# mcu_brd2.net
KiCad netlist of a schematic drawn in EAGLE
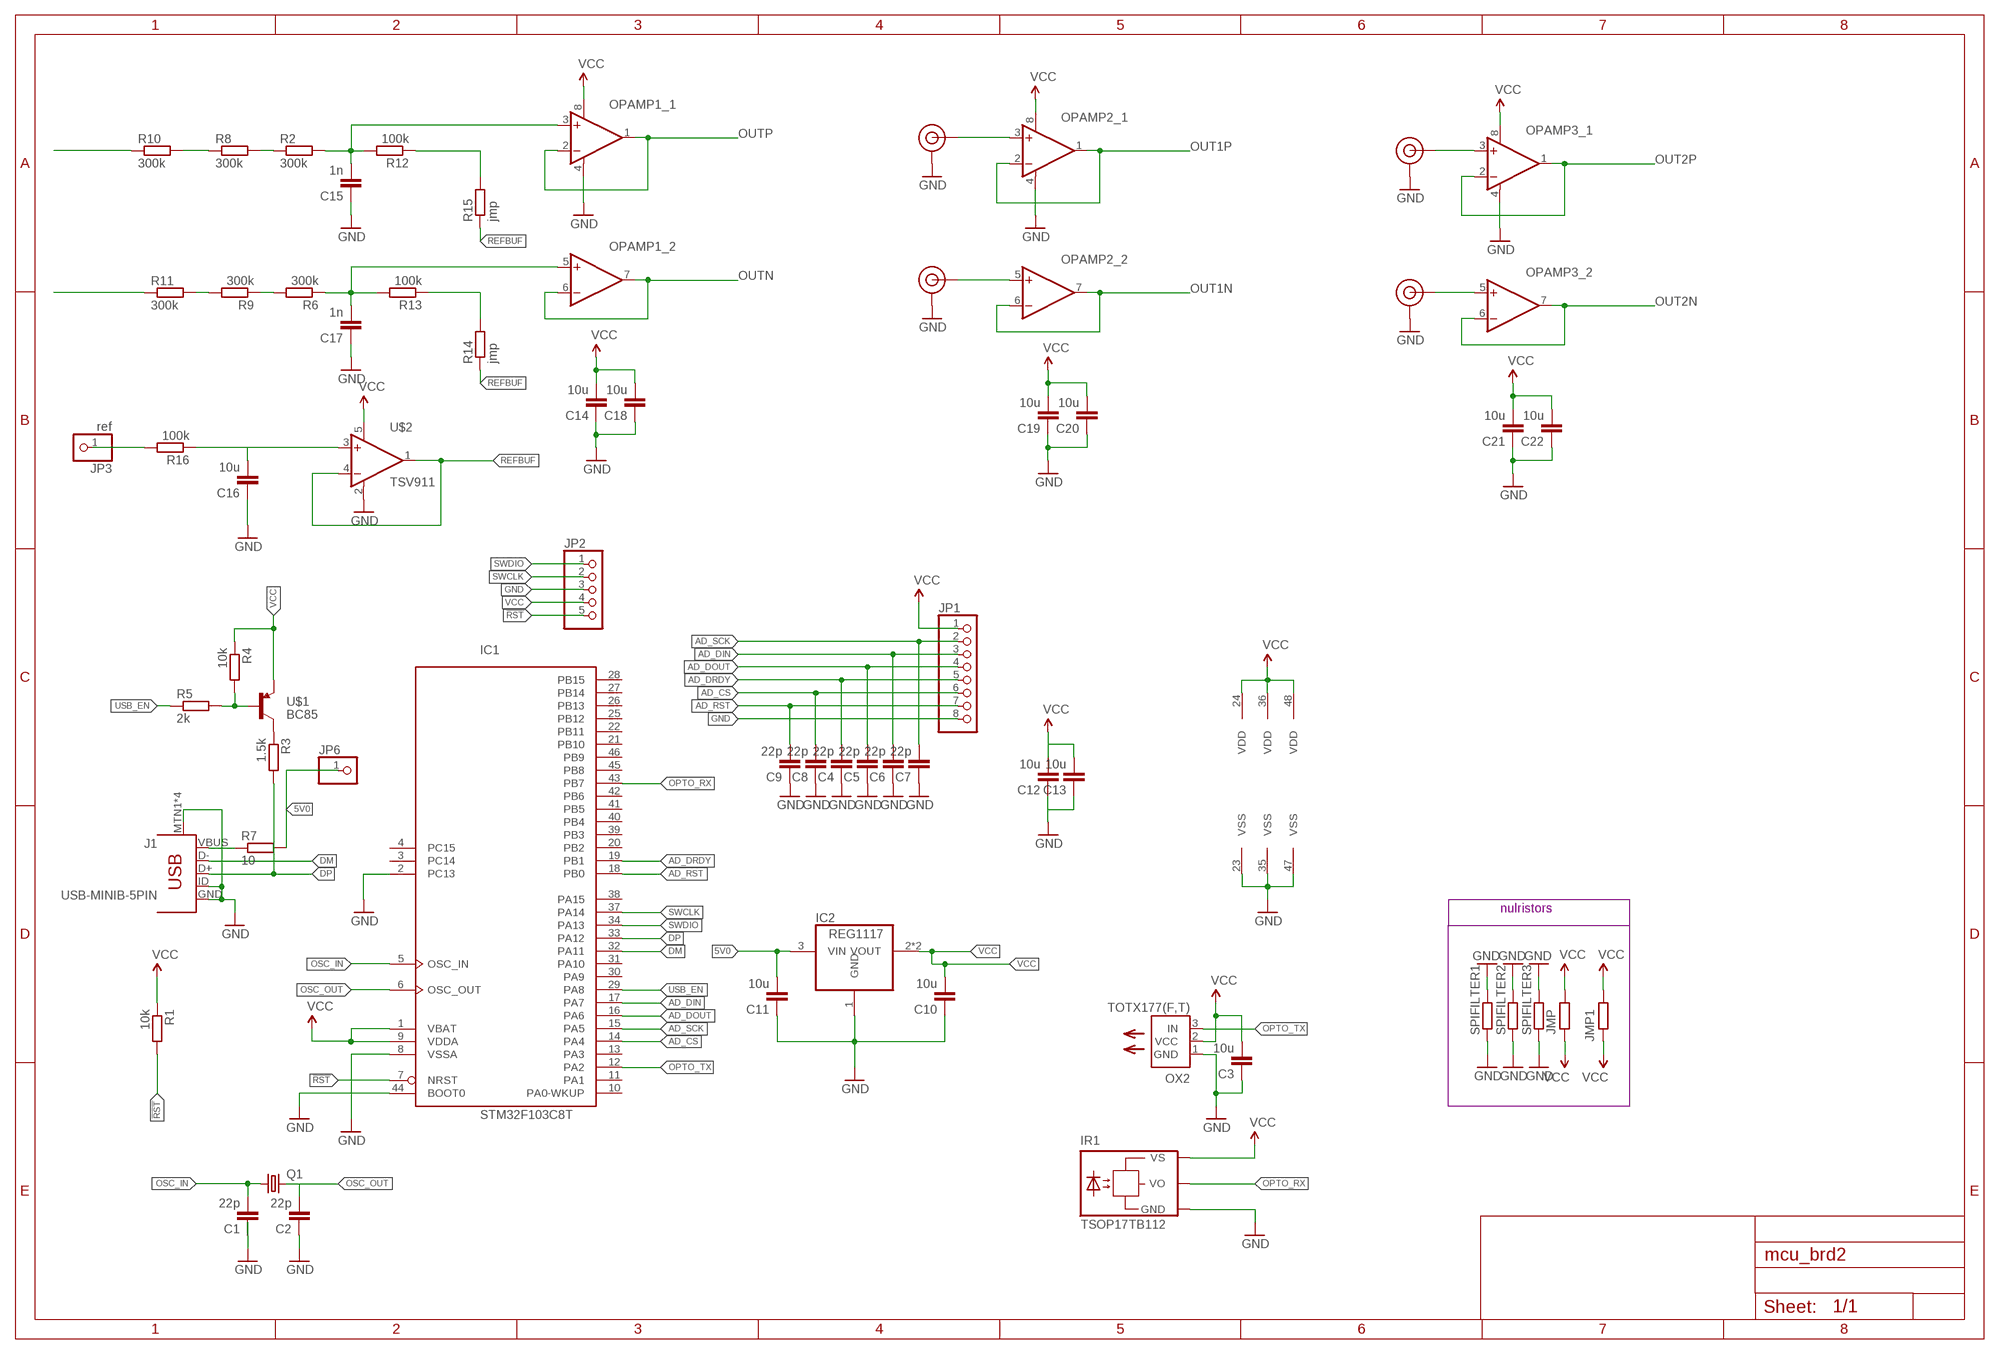
[diagram p0: schematic, sheet 1]

(export (version "E")
  (design (tool "Eeschema 10.0.6"))
  (components
    (comp (ref "C1")
      (value "22p")
      (footprint "eagle-import:C0603")
      (libsource (lib "eagle-import") (part "CC0603"))
    )
    (comp (ref "C2")
      (value "22p")
      (footprint "eagle-import:C0603")
      (libsource (lib "eagle-import") (part "CC0603"))
    )
    (comp (ref "C3")
      (value "10u")
      (footprint "eagle-import:C0603")
      (libsource (lib "eagle-import") (part "CC0603"))
    )
    (comp (ref "C4")
      (value "22p")
      (footprint "eagle-import:C0603")
      (libsource (lib "eagle-import") (part "CC0603"))
    )
    (comp (ref "C5")
      (value "22p")
      (footprint "eagle-import:C0603")
      (libsource (lib "eagle-import") (part "CC0603"))
    )
    (comp (ref "C6")
      (value "22p")
      (footprint "eagle-import:C0603")
      (libsource (lib "eagle-import") (part "CC0603"))
    )
    (comp (ref "C7")
      (value "22p")
      (footprint "eagle-import:C0603")
      (libsource (lib "eagle-import") (part "CC0603"))
    )
    (comp (ref "C8")
      (value "22p")
      (footprint "eagle-import:C0603")
      (libsource (lib "eagle-import") (part "CC0603"))
    )
    (comp (ref "C9")
      (value "22p")
      (footprint "eagle-import:C0603")
      (libsource (lib "eagle-import") (part "CC0603"))
    )
    (comp (ref "C10")
      (value "10u")
      (footprint "eagle-import:C0805")
      (libsource (lib "eagle-import") (part "CC0805"))
    )
    (comp (ref "C11")
      (value "10u")
      (footprint "eagle-import:C0805")
      (libsource (lib "eagle-import") (part "CC0805"))
    )
    (comp (ref "C12")
      (value "10u")
      (footprint "eagle-import:C0805")
      (libsource (lib "eagle-import") (part "CC0805"))
    )
    (comp (ref "C13")
      (value "10u")
      (footprint "eagle-import:C0805")
      (libsource (lib "eagle-import") (part "CC0805"))
    )
    (comp (ref "C14")
      (value "10u")
      (footprint "eagle-import:C0805")
      (libsource (lib "eagle-import") (part "CC0805"))
    )
    (comp (ref "C15")
      (value "1n")
      (footprint "eagle-import:C0603")
      (libsource (lib "eagle-import") (part "CC0603"))
    )
    (comp (ref "C16")
      (value "10u")
      (footprint "eagle-import:C0805")
      (libsource (lib "eagle-import") (part "CC0805"))
    )
    (comp (ref "C17")
      (value "1n")
      (footprint "eagle-import:C0603")
      (libsource (lib "eagle-import") (part "CC0603"))
    )
    (comp (ref "C18")
      (value "10u")
      (footprint "eagle-import:C0805")
      (libsource (lib "eagle-import") (part "CC0805"))
    )
    (comp (ref "C19")
      (value "10u")
      (footprint "eagle-import:C0805")
      (libsource (lib "eagle-import") (part "CC0805"))
    )
    (comp (ref "C20")
      (value "10u")
      (footprint "eagle-import:C0805")
      (libsource (lib "eagle-import") (part "CC0805"))
    )
    (comp (ref "C21")
      (value "10u")
      (footprint "eagle-import:C0805")
      (libsource (lib "eagle-import") (part "CC0805"))
    )
    (comp (ref "C22")
      (value "10u")
      (footprint "eagle-import:C0805")
      (libsource (lib "eagle-import") (part "CC0805"))
    )
    (comp (ref "IC1")
      (value "STM32F103C8T")
      (footprint "eagle-import:LQFP48")
      (libsource (lib "eagle-import") (part "STM32F103CT8"))
    )
    (comp (ref "IC2")
      (value "REG1117")
      (footprint "eagle-import:SOT223")
      (libsource (lib "eagle-import") (part "REG1117"))
    )
    (comp (ref "IR1")
      (value "TSOP17TB112")
      (footprint "eagle-import:1X03")
      (libsource (lib "eagle-import") (part "TSOP17TB112"))
    )
    (comp (ref "J$1")
      (value "SMA_EDGE")
      (footprint "eagle-import:SMA-EDGE")
      (libsource (lib "eagle-import") (part "SMA_EDGE"))
    )
    (comp (ref "J$2")
      (value "SMA_EDGE")
      (footprint "eagle-import:SMA-EDGE")
      (libsource (lib "eagle-import") (part "SMA_EDGE"))
    )
    (comp (ref "J$3")
      (value "SMA_EDGE")
      (footprint "eagle-import:SMA-EDGE")
      (libsource (lib "eagle-import") (part "SMA_EDGE"))
    )
    (comp (ref "J$4")
      (value "SMA_EDGE")
      (footprint "eagle-import:SMA-EDGE")
      (libsource (lib "eagle-import") (part "SMA_EDGE"))
    )
    (comp (ref "J1")
      (value "USB-MINIB-5PIN")
      (footprint "eagle-import:USB-MINIB")
      (libsource (lib "eagle-import") (part "USB-MINIB-5PIN"))
    )
    (comp (ref "JMP")
      (value "R0603")
      (footprint "eagle-import:0603")
      (libsource (lib "eagle-import") (part "R0603"))
    )
    (comp (ref "JMP1")
      (value "R0603")
      (footprint "eagle-import:0603")
      (libsource (lib "eagle-import") (part "R0603"))
    )
    (comp (ref "JP1")
      (value "PINHD-1X8")
      (footprint "eagle-import:1X08")
      (libsource (lib "eagle-import") (part "PINHD-1X8"))
    )
    (comp (ref "JP2")
      (value "PINHD-1X5")
      (footprint "eagle-import:1X05")
      (libsource (lib "eagle-import") (part "PINHD-1X5"))
    )
    (comp (ref "JP3")
      (value "ref")
      (footprint "eagle-import:1X01M")
      (libsource (lib "eagle-import") (part "PINHD-1X01_2.00"))
    )
    (comp (ref "JP6")
      (value "PINHD-1X1")
      (footprint "eagle-import:1X01")
      (libsource (lib "eagle-import") (part "PINHD-1X1"))
    )
    (comp (ref "OPAMP1")
      (value "LMC662")
      (footprint "eagle-import:SO08")
      (libsource (lib "eagle-import") (part "LMC662"))
    )
    (comp (ref "OPAMP2")
      (value "LMC662")
      (footprint "eagle-import:SO08")
      (libsource (lib "eagle-import") (part "LMC662"))
    )
    (comp (ref "OPAMP3")
      (value "LMC662")
      (footprint "eagle-import:SO08")
      (libsource (lib "eagle-import") (part "LMC662"))
    )
    (comp (ref "OX2")
      (value "TOTX177(F,T)")
      (footprint "eagle-import:TOTX")
      (libsource (lib "eagle-import") (part "TOTX177(F,T)"))
    )
    (comp (ref "Q1")
      (value "CRYSTALHC49UP")
      (footprint "eagle-import:HC49UP")
      (libsource (lib "eagle-import") (part "CRYSTALHC49UP"))
    )
    (comp (ref "R1")
      (value "10k")
      (footprint "eagle-import:0603")
      (libsource (lib "eagle-import") (part "R0603"))
    )
    (comp (ref "R2")
      (value "300k")
      (footprint "eagle-import:0603")
      (libsource (lib "eagle-import") (part "R0603"))
    )
    (comp (ref "R3")
      (value "1.5k")
      (footprint "eagle-import:0603")
      (libsource (lib "eagle-import") (part "R0603"))
    )
    (comp (ref "R4")
      (value "10k")
      (footprint "eagle-import:0603")
      (libsource (lib "eagle-import") (part "R0603"))
    )
    (comp (ref "R5")
      (value "2k")
      (footprint "eagle-import:0603")
      (libsource (lib "eagle-import") (part "R0603"))
    )
    (comp (ref "R6")
      (value "300k")
      (footprint "eagle-import:0603")
      (libsource (lib "eagle-import") (part "R0603"))
    )
    (comp (ref "R7")
      (value "10")
      (footprint "eagle-import:R0805")
      (libsource (lib "eagle-import") (part "R0805"))
    )
    (comp (ref "R8")
      (value "300k")
      (footprint "eagle-import:0603")
      (libsource (lib "eagle-import") (part "R0603"))
    )
    (comp (ref "R9")
      (value "300k")
      (footprint "eagle-import:0603")
      (libsource (lib "eagle-import") (part "R0603"))
    )
    (comp (ref "R10")
      (value "300k")
      (footprint "eagle-import:0603")
      (libsource (lib "eagle-import") (part "R0603"))
    )
    (comp (ref "R11")
      (value "300k")
      (footprint "eagle-import:0603")
      (libsource (lib "eagle-import") (part "R0603"))
    )
    (comp (ref "R12")
      (value "100k")
      (footprint "eagle-import:0603")
      (libsource (lib "eagle-import") (part "R0603"))
    )
    (comp (ref "R13")
      (value "100k")
      (footprint "eagle-import:0603")
      (libsource (lib "eagle-import") (part "R0603"))
    )
    (comp (ref "R14")
      (value "jmp")
      (footprint "eagle-import:0603")
      (libsource (lib "eagle-import") (part "R0603"))
    )
    (comp (ref "R15")
      (value "jmp")
      (footprint "eagle-import:0603")
      (libsource (lib "eagle-import") (part "R0603"))
    )
    (comp (ref "R16")
      (value "100k")
      (footprint "eagle-import:0603")
      (libsource (lib "eagle-import") (part "R0603"))
    )
    (comp (ref "SPIFILTER1")
      (value "R0603")
      (footprint "eagle-import:0603")
      (libsource (lib "eagle-import") (part "R0603"))
    )
    (comp (ref "SPIFILTER2")
      (value "R0603")
      (footprint "eagle-import:0603")
      (libsource (lib "eagle-import") (part "R0603"))
    )
    (comp (ref "SPIFILTER3")
      (value "R0603")
      (footprint "eagle-import:0603")
      (libsource (lib "eagle-import") (part "R0603"))
    )
    (comp (ref "U$1")
      (value "BC85")
      (footprint "eagle-import:SOT23")
      (libsource (lib "eagle-import") (part "BC85"))
    )
    (comp (ref "U$2")
      (value "TSV911")
      (footprint "eagle-import:SOT23-5L")
      (libsource (lib "eagle-import") (part "TSV911"))
    )
  )
  (nets
    (net (code "1") (name "/OUT1N") (class "Default")
      (node (ref "OPAMP2") (pin "6") (pinfunction "-IN_6") (pintype "input"))
      (node (ref "OPAMP2") (pin "7") (pinfunction "OUT_7") (pintype "output"))
    )
    (net (code "2") (name "/OUT1P") (class "Default")
      (node (ref "OPAMP2") (pin "1") (pinfunction "OUT_1") (pintype "output"))
      (node (ref "OPAMP2") (pin "2") (pinfunction "-IN_2") (pintype "input"))
    )
    (net (code "3") (name "/OUT2N") (class "Default")
      (node (ref "OPAMP3") (pin "6") (pinfunction "-IN_6") (pintype "input"))
      (node (ref "OPAMP3") (pin "7") (pinfunction "OUT_7") (pintype "output"))
    )
    (net (code "4") (name "/OUT2P") (class "Default")
      (node (ref "OPAMP3") (pin "1") (pinfunction "OUT_1") (pintype "output"))
      (node (ref "OPAMP3") (pin "2") (pinfunction "-IN_2") (pintype "input"))
    )
    (net (code "5") (name "/OUTN") (class "Default")
      (node (ref "OPAMP1") (pin "6") (pinfunction "-IN_6") (pintype "input"))
      (node (ref "OPAMP1") (pin "7") (pinfunction "OUT_7") (pintype "output"))
    )
    (net (code "6") (name "/OUTP") (class "Default")
      (node (ref "OPAMP1") (pin "1") (pinfunction "OUT_1") (pintype "output"))
      (node (ref "OPAMP1") (pin "2") (pinfunction "-IN_2") (pintype "input"))
    )
    (net (code "7") (name "/~{RST}") (class "Default")
      (node (ref "IC1") (pin "7") (pinfunction "NRST_7") (pintype "bidirectional"))
      (node (ref "JP2") (pin "5") (pinfunction "5_5") (pintype "passive"))
      (node (ref "R1") (pin "2") (pinfunction "2_2") (pintype "passive"))
    )
    (net (code "8") (name "5V0") (class "Default")
      (node (ref "C11") (pin "2") (pinfunction "2_2") (pintype "passive"))
      (node (ref "IC2") (pin "3") (pinfunction "VIN_3") (pintype "input"))
      (node (ref "JP6") (pin "1") (pinfunction "1_1") (pintype "passive"))
      (node (ref "R7") (pin "2") (pinfunction "2_2") (pintype "passive"))
    )
    (net (code "9") (name "AD_CS") (class "Default")
      (node (ref "C8") (pin "2") (pinfunction "2_2") (pintype "passive"))
      (node (ref "IC1") (pin "14") (pinfunction "PA4_14") (pintype "bidirectional"))
      (node (ref "JP1") (pin "6") (pinfunction "6_6") (pintype "passive"))
    )
    (net (code "10") (name "AD_DIN") (class "Default")
      (node (ref "C6") (pin "2") (pinfunction "2_2") (pintype "passive"))
      (node (ref "IC1") (pin "17") (pinfunction "PA7_17") (pintype "bidirectional"))
      (node (ref "JP1") (pin "3") (pinfunction "3_3") (pintype "passive"))
    )
    (net (code "11") (name "AD_DOUT") (class "Default")
      (node (ref "C5") (pin "2") (pinfunction "2_2") (pintype "passive"))
      (node (ref "IC1") (pin "16") (pinfunction "PA6_16") (pintype "bidirectional"))
      (node (ref "JP1") (pin "4") (pinfunction "4_4") (pintype "passive"))
    )
    (net (code "12") (name "AD_DRDY") (class "Default")
      (node (ref "C4") (pin "2") (pinfunction "2_2") (pintype "passive"))
      (node (ref "IC1") (pin "19") (pinfunction "PB1_19") (pintype "bidirectional"))
      (node (ref "JP1") (pin "5") (pinfunction "5_5") (pintype "passive"))
    )
    (net (code "13") (name "AD_RST") (class "Default")
      (node (ref "C9") (pin "2") (pinfunction "2_2") (pintype "passive"))
      (node (ref "IC1") (pin "18") (pinfunction "PB0_18") (pintype "bidirectional"))
      (node (ref "JP1") (pin "7") (pinfunction "7_7") (pintype "passive"))
    )
    (net (code "14") (name "AD_SCK") (class "Default")
      (node (ref "C7") (pin "2") (pinfunction "2_2") (pintype "passive"))
      (node (ref "IC1") (pin "15") (pinfunction "PA5_15") (pintype "bidirectional"))
      (node (ref "JP1") (pin "2") (pinfunction "2_2") (pintype "passive"))
    )
    (net (code "15") (name "DM") (class "Default")
      (node (ref "IC1") (pin "32") (pinfunction "PA11_32") (pintype "bidirectional"))
      (node (ref "J1") (pin "D-") (pinfunction "D-_D-") (pintype "bidirectional"))
    )
    (net (code "16") (name "DP") (class "Default")
      (node (ref "IC1") (pin "33") (pinfunction "PA12_33") (pintype "bidirectional"))
      (node (ref "J1") (pin "D+") (pinfunction "D+_D+") (pintype "bidirectional"))
      (node (ref "R3") (pin "2") (pinfunction "2_2") (pintype "passive"))
    )
    (net (code "17") (name "GND") (class "Default")
      (node (ref "C1") (pin "1") (pinfunction "1_1") (pintype "passive"))
      (node (ref "C10") (pin "1") (pinfunction "1_1") (pintype "passive"))
      (node (ref "C11") (pin "1") (pinfunction "1_1") (pintype "passive"))
      (node (ref "C12") (pin "1") (pinfunction "1_1") (pintype "passive"))
      (node (ref "C13") (pin "1") (pinfunction "1_1") (pintype "passive"))
      (node (ref "C14") (pin "1") (pinfunction "1_1") (pintype "passive"))
      (node (ref "C15") (pin "1") (pinfunction "1_1") (pintype "passive"))
      (node (ref "C16") (pin "1") (pinfunction "1_1") (pintype "passive"))
      (node (ref "C17") (pin "1") (pinfunction "1_1") (pintype "passive"))
      (node (ref "C18") (pin "1") (pinfunction "1_1") (pintype "passive"))
      (node (ref "C19") (pin "1") (pinfunction "1_1") (pintype "passive"))
      (node (ref "C2") (pin "1") (pinfunction "1_1") (pintype "passive"))
      (node (ref "C20") (pin "1") (pinfunction "1_1") (pintype "passive"))
      (node (ref "C21") (pin "1") (pinfunction "1_1") (pintype "passive"))
      (node (ref "C22") (pin "1") (pinfunction "1_1") (pintype "passive"))
      (node (ref "C3") (pin "1") (pinfunction "1_1") (pintype "passive"))
      (node (ref "C4") (pin "1") (pinfunction "1_1") (pintype "passive"))
      (node (ref "C5") (pin "1") (pinfunction "1_1") (pintype "passive"))
      (node (ref "C6") (pin "1") (pinfunction "1_1") (pintype "passive"))
      (node (ref "C7") (pin "1") (pinfunction "1_1") (pintype "passive"))
      (node (ref "C8") (pin "1") (pinfunction "1_1") (pintype "passive"))
      (node (ref "C9") (pin "1") (pinfunction "1_1") (pintype "passive"))
      (node (ref "IC1") (pin "2") (pinfunction "PC13_2") (pintype "bidirectional"))
      (node (ref "IC1") (pin "23") (pinfunction "VSS_23") (pintype "power_in"))
      (node (ref "IC1") (pin "35") (pinfunction "VSS_35") (pintype "power_in"))
      (node (ref "IC1") (pin "44") (pinfunction "BOOT0_44") (pintype "input"))
      (node (ref "IC1") (pin "47") (pinfunction "VSS_47") (pintype "power_in"))
      (node (ref "IC1") (pin "8") (pinfunction "VSSA_8") (pintype "power_in"))
      (node (ref "IC2") (pin "1") (pinfunction "GND_1") (pintype "power_in"))
      (node (ref "IR1") (pin "3") (pinfunction "GND_3") (pintype "power_in"))
      (node (ref "J$1") (pin "GND@0") (pinfunction "GND_GND@0") (pintype "bidirectional"))
      (node (ref "J$1") (pin "GND@1") (pinfunction "GND_GND@1") (pintype "bidirectional"))
      (node (ref "J$1") (pin "GND@2") (pinfunction "GND_GND@2") (pintype "bidirectional"))
      (node (ref "J$1") (pin "GND@3") (pinfunction "GND_GND@3") (pintype "bidirectional"))
      (node (ref "J$2") (pin "GND@0") (pinfunction "GND_GND@0") (pintype "bidirectional"))
      (node (ref "J$2") (pin "GND@1") (pinfunction "GND_GND@1") (pintype "bidirectional"))
      (node (ref "J$2") (pin "GND@2") (pinfunction "GND_GND@2") (pintype "bidirectional"))
      (node (ref "J$2") (pin "GND@3") (pinfunction "GND_GND@3") (pintype "bidirectional"))
      (node (ref "J$3") (pin "GND@0") (pinfunction "GND_GND@0") (pintype "bidirectional"))
      (node (ref "J$3") (pin "GND@1") (pinfunction "GND_GND@1") (pintype "bidirectional"))
      (node (ref "J$3") (pin "GND@2") (pinfunction "GND_GND@2") (pintype "bidirectional"))
      (node (ref "J$3") (pin "GND@3") (pinfunction "GND_GND@3") (pintype "bidirectional"))
      (node (ref "J$4") (pin "GND@0") (pinfunction "GND_GND@0") (pintype "bidirectional"))
      (node (ref "J$4") (pin "GND@1") (pinfunction "GND_GND@1") (pintype "bidirectional"))
      (node (ref "J$4") (pin "GND@2") (pinfunction "GND_GND@2") (pintype "bidirectional"))
      (node (ref "J$4") (pin "GND@3") (pinfunction "GND_GND@3") (pintype "bidirectional"))
      (node (ref "J1") (pin "GND") (pinfunction "GND_GND") (pintype "bidirectional"))
      (node (ref "J1") (pin "ID") (pinfunction "ID_ID") (pintype "bidirectional"))
      (node (ref "J1") (pin "MTN1") (pinfunction "MTN1_MTN1") (pintype "bidirectional"))
      (node (ref "J1") (pin "MTN2") (pinfunction "MTN1_MTN2") (pintype "bidirectional"))
      (node (ref "J1") (pin "MTN3") (pinfunction "MTN1_MTN3") (pintype "bidirectional"))
      (node (ref "J1") (pin "MTN4") (pinfunction "MTN1_MTN4") (pintype "bidirectional"))
      (node (ref "JP1") (pin "8") (pinfunction "8_8") (pintype "passive"))
      (node (ref "JP2") (pin "3") (pinfunction "3_3") (pintype "passive"))
      (node (ref "OPAMP1") (pin "4") (pinfunction "V-_4") (pintype "power_in"))
      (node (ref "OPAMP2") (pin "4") (pinfunction "V-_4") (pintype "power_in"))
      (node (ref "OPAMP3") (pin "4") (pinfunction "V-_4") (pintype "power_in"))
      (node (ref "OX2") (pin "1") (pinfunction "GND_1") (pintype "power_in"))
      (node (ref "SPIFILTER1") (pin "1") (pinfunction "1_1") (pintype "passive"))
      (node (ref "SPIFILTER1") (pin "2") (pinfunction "2_2") (pintype "passive"))
      (node (ref "SPIFILTER2") (pin "1") (pinfunction "1_1") (pintype "passive"))
      (node (ref "SPIFILTER2") (pin "2") (pinfunction "2_2") (pintype "passive"))
      (node (ref "SPIFILTER3") (pin "1") (pinfunction "1_1") (pintype "passive"))
      (node (ref "SPIFILTER3") (pin "2") (pinfunction "2_2") (pintype "passive"))
      (node (ref "U$2") (pin "2") (pinfunction "V-_2") (pintype "power_in"))
    )
    (net (code "18") (name "Net-(J$1-SIGNAL)") (class "Default")
      (node (ref "J$1") (pin "SIG") (pinfunction "SIGNAL_SIG") (pintype "bidirectional"))
      (node (ref "OPAMP2") (pin "3") (pinfunction "+IN_3") (pintype "input"))
    )
    (net (code "19") (name "Net-(J$2-SIGNAL)") (class "Default")
      (node (ref "J$2") (pin "SIG") (pinfunction "SIGNAL_SIG") (pintype "bidirectional"))
      (node (ref "OPAMP2") (pin "5") (pinfunction "+IN_5") (pintype "input"))
    )
    (net (code "20") (name "Net-(J$3-SIGNAL)") (class "Default")
      (node (ref "J$3") (pin "SIG") (pinfunction "SIGNAL_SIG") (pintype "bidirectional"))
      (node (ref "OPAMP3") (pin "3") (pinfunction "+IN_3") (pintype "input"))
    )
    (net (code "21") (name "Net-(J$4-SIGNAL)") (class "Default")
      (node (ref "J$4") (pin "SIG") (pinfunction "SIGNAL_SIG") (pintype "bidirectional"))
      (node (ref "OPAMP3") (pin "5") (pinfunction "+IN_5") (pintype "input"))
    )
    (net (code "22") (name "Net-(J1-PadVBUS)") (class "Default")
      (node (ref "J1") (pin "VBUS") (pinfunction "VBUS_VBUS") (pintype "bidirectional"))
      (node (ref "R7") (pin "1") (pinfunction "1_1") (pintype "passive"))
    )
    (net (code "23") (name "Net-(JP3-Pad1)") (class "Default")
      (node (ref "JP3") (pin "1") (pinfunction "1_1") (pintype "passive"))
      (node (ref "R16") (pin "2") (pinfunction "2_2") (pintype "passive"))
    )
    (net (code "24") (name "Net-(OPAMP1A-+IN)") (class "Default")
      (node (ref "C15") (pin "2") (pinfunction "2_2") (pintype "passive"))
      (node (ref "OPAMP1") (pin "3") (pinfunction "+IN_3") (pintype "input"))
      (node (ref "R12") (pin "2") (pinfunction "2_2") (pintype "passive"))
      (node (ref "R2") (pin "2") (pinfunction "2_2") (pintype "passive"))
    )
    (net (code "25") (name "Net-(OPAMP1B-+IN)") (class "Default")
      (node (ref "C17") (pin "2") (pinfunction "2_2") (pintype "passive"))
      (node (ref "OPAMP1") (pin "5") (pinfunction "+IN_5") (pintype "input"))
      (node (ref "R13") (pin "2") (pinfunction "2_2") (pintype "passive"))
      (node (ref "R6") (pin "1") (pinfunction "1_1") (pintype "passive"))
    )
    (net (code "26") (name "Net-(R2-Pad1)") (class "Default")
      (node (ref "R2") (pin "1") (pinfunction "1_1") (pintype "passive"))
      (node (ref "R8") (pin "2") (pinfunction "2_2") (pintype "passive"))
    )
    (net (code "27") (name "Net-(R6-Pad2)") (class "Default")
      (node (ref "R6") (pin "2") (pinfunction "2_2") (pintype "passive"))
      (node (ref "R9") (pin "1") (pinfunction "1_1") (pintype "passive"))
    )
    (net (code "28") (name "Net-(R10-Pad2)") (class "Default")
      (node (ref "R10") (pin "2") (pinfunction "2_2") (pintype "passive"))
      (node (ref "R8") (pin "1") (pinfunction "1_1") (pintype "passive"))
    )
    (net (code "29") (name "Net-(R11-Pad2)") (class "Default")
      (node (ref "R11") (pin "2") (pinfunction "2_2") (pintype "passive"))
      (node (ref "R9") (pin "2") (pinfunction "2_2") (pintype "passive"))
    )
    (net (code "30") (name "Net-(R12-Pad1)") (class "Default")
      (node (ref "R12") (pin "1") (pinfunction "1_1") (pintype "passive"))
      (node (ref "R15") (pin "2") (pinfunction "2_2") (pintype "passive"))
    )
    (net (code "31") (name "Net-(R13-Pad1)") (class "Default")
      (node (ref "R13") (pin "1") (pinfunction "1_1") (pintype "passive"))
      (node (ref "R14") (pin "2") (pinfunction "2_2") (pintype "passive"))
    )
    (net (code "32") (name "Net-(U$1-B)") (class "Default")
      (node (ref "R4") (pin "2") (pinfunction "2_2") (pintype "passive"))
      (node (ref "R5") (pin "2") (pinfunction "2_2") (pintype "passive"))
      (node (ref "U$1") (pin "1") (pinfunction "B_1") (pintype "passive"))
    )
    (net (code "33") (name "Net-(U$1-C)") (class "Default")
      (node (ref "R3") (pin "1") (pinfunction "1_1") (pintype "passive"))
      (node (ref "U$1") (pin "3") (pinfunction "C_3") (pintype "passive"))
    )
    (net (code "34") (name "Net-(U$2-+IN)") (class "Default")
      (node (ref "C16") (pin "2") (pinfunction "2_2") (pintype "passive"))
      (node (ref "R16") (pin "1") (pinfunction "1_1") (pintype "passive"))
      (node (ref "U$2") (pin "3") (pinfunction "+IN_3") (pintype "input"))
    )
    (net (code "35") (name "OPTO_RX") (class "Default")
      (node (ref "IC1") (pin "43") (pinfunction "PB7_43") (pintype "bidirectional"))
      (node (ref "IR1") (pin "1") (pinfunction "VO_1") (pintype "open_collector"))
    )
    (net (code "36") (name "OPTO_TX") (class "Default")
      (node (ref "IC1") (pin "12") (pinfunction "PA2_12") (pintype "bidirectional"))
      (node (ref "OX2") (pin "3") (pinfunction "IN_3") (pintype "input"))
    )
    (net (code "37") (name "OSC_IN") (class "Default")
      (node (ref "C1") (pin "2") (pinfunction "2_2") (pintype "passive"))
      (node (ref "IC1") (pin "5") (pinfunction "OSC_IN_5") (pintype "bidirectional"))
      (node (ref "Q1") (pin "1") (pinfunction "1_1") (pintype "passive"))
    )
    (net (code "38") (name "OSC_OUT") (class "Default")
      (node (ref "C2") (pin "2") (pinfunction "2_2") (pintype "passive"))
      (node (ref "IC1") (pin "6") (pinfunction "OSC_OUT_6") (pintype "bidirectional"))
      (node (ref "Q1") (pin "2") (pinfunction "2_2") (pintype "passive"))
    )
    (net (code "39") (name "REFBUF") (class "Default")
      (node (ref "R14") (pin "1") (pinfunction "1_1") (pintype "passive"))
      (node (ref "R15") (pin "1") (pinfunction "1_1") (pintype "passive"))
      (node (ref "U$2") (pin "1") (pinfunction "OUT_1") (pintype "output"))
      (node (ref "U$2") (pin "4") (pinfunction "-IN_4") (pintype "input"))
    )
    (net (code "40") (name "SWCLK") (class "Default")
      (node (ref "IC1") (pin "37") (pinfunction "PA14_37") (pintype "bidirectional"))
      (node (ref "JP2") (pin "2") (pinfunction "2_2") (pintype "passive"))
    )
    (net (code "41") (name "SWDIO") (class "Default")
      (node (ref "IC1") (pin "34") (pinfunction "PA13_34") (pintype "bidirectional"))
      (node (ref "JP2") (pin "1") (pinfunction "1_1") (pintype "passive"))
    )
    (net (code "42") (name "USB_EN") (class "Default")
      (node (ref "IC1") (pin "29") (pinfunction "PA8_29") (pintype "bidirectional"))
      (node (ref "R5") (pin "1") (pinfunction "1_1") (pintype "passive"))
    )
    (net (code "43") (name "VCC") (class "Default")
      (node (ref "C10") (pin "2") (pinfunction "2_2") (pintype "passive"))
      (node (ref "C12") (pin "2") (pinfunction "2_2") (pintype "passive"))
      (node (ref "C13") (pin "2") (pinfunction "2_2") (pintype "passive"))
      (node (ref "C14") (pin "2") (pinfunction "2_2") (pintype "passive"))
      (node (ref "C18") (pin "2") (pinfunction "2_2") (pintype "passive"))
      (node (ref "C19") (pin "2") (pinfunction "2_2") (pintype "passive"))
      (node (ref "C20") (pin "2") (pinfunction "2_2") (pintype "passive"))
      (node (ref "C21") (pin "2") (pinfunction "2_2") (pintype "passive"))
      (node (ref "C22") (pin "2") (pinfunction "2_2") (pintype "passive"))
      (node (ref "C3") (pin "2") (pinfunction "2_2") (pintype "passive"))
      (node (ref "IC1") (pin "1") (pinfunction "VBAT_1") (pintype "power_in"))
      (node (ref "IC1") (pin "24") (pinfunction "VDD_24") (pintype "power_in"))
      (node (ref "IC1") (pin "36") (pinfunction "VDD_36") (pintype "power_in"))
      (node (ref "IC1") (pin "48") (pinfunction "VDD_48") (pintype "power_in"))
      (node (ref "IC1") (pin "9") (pinfunction "VDDA_9") (pintype "power_in"))
      (node (ref "IC2") (pin "2") (pinfunction "VOUT_2") (pintype "output"))
      (node (ref "IC2") (pin "4") (pinfunction "VOUT_4") (pintype "output"))
      (node (ref "IR1") (pin "2") (pinfunction "VS_2") (pintype "power_in"))
      (node (ref "JMP") (pin "1") (pinfunction "1_1") (pintype "passive"))
      (node (ref "JMP") (pin "2") (pinfunction "2_2") (pintype "passive"))
      (node (ref "JMP1") (pin "1") (pinfunction "1_1") (pintype "passive"))
      (node (ref "JMP1") (pin "2") (pinfunction "2_2") (pintype "passive"))
      (node (ref "JP1") (pin "1") (pinfunction "1_1") (pintype "passive"))
      (node (ref "JP2") (pin "4") (pinfunction "4_4") (pintype "passive"))
      (node (ref "OPAMP1") (pin "8") (pinfunction "V+_8") (pintype "power_in"))
      (node (ref "OPAMP2") (pin "8") (pinfunction "V+_8") (pintype "power_in"))
      (node (ref "OPAMP3") (pin "8") (pinfunction "V+_8") (pintype "power_in"))
      (node (ref "OX2") (pin "2") (pinfunction "VCC_2") (pintype "power_in"))
      (node (ref "R1") (pin "1") (pinfunction "1_1") (pintype "passive"))
      (node (ref "R4") (pin "1") (pinfunction "1_1") (pintype "passive"))
      (node (ref "U$1") (pin "2") (pinfunction "E_2") (pintype "passive"))
      (node (ref "U$2") (pin "5") (pinfunction "V+_5") (pintype "power_in"))
    )
    (net (code "44") (name "unconnected-(IC1A-PA0-WKUP-Pad10)") (class "Default")
      (node (ref "IC1") (pin "10") (pinfunction "PA0-WKUP_10") (pintype "bidirectional"))
    )
    (net (code "45") (name "unconnected-(IC1A-PA1-Pad11)") (class "Default")
      (node (ref "IC1") (pin "11") (pinfunction "PA1_11") (pintype "bidirectional"))
    )
    (net (code "46") (name "unconnected-(IC1A-PA3-Pad13)") (class "Default")
      (node (ref "IC1") (pin "13") (pinfunction "PA3_13") (pintype "bidirectional"))
    )
    (net (code "47") (name "unconnected-(IC1A-PA9-Pad30)") (class "Default")
      (node (ref "IC1") (pin "30") (pinfunction "PA9_30") (pintype "bidirectional"))
    )
    (net (code "48") (name "unconnected-(IC1A-PA10-Pad31)") (class "Default")
      (node (ref "IC1") (pin "31") (pinfunction "PA10_31") (pintype "bidirectional"))
    )
    (net (code "49") (name "unconnected-(IC1A-PA15-Pad38)") (class "Default")
      (node (ref "IC1") (pin "38") (pinfunction "PA15_38") (pintype "bidirectional"))
    )
    (net (code "50") (name "unconnected-(IC1A-PB2-Pad20)") (class "Default")
      (node (ref "IC1") (pin "20") (pinfunction "PB2_20") (pintype "bidirectional"))
    )
    (net (code "51") (name "unconnected-(IC1A-PB3-Pad39)") (class "Default")
      (node (ref "IC1") (pin "39") (pinfunction "PB3_39") (pintype "bidirectional"))
    )
    (net (code "52") (name "unconnected-(IC1A-PB4-Pad40)") (class "Default")
      (node (ref "IC1") (pin "40") (pinfunction "PB4_40") (pintype "bidirectional"))
    )
    (net (code "53") (name "unconnected-(IC1A-PB5-Pad41)") (class "Default")
      (node (ref "IC1") (pin "41") (pinfunction "PB5_41") (pintype "bidirectional"))
    )
    (net (code "54") (name "unconnected-(IC1A-PB6-Pad42)") (class "Default")
      (node (ref "IC1") (pin "42") (pinfunction "PB6_42") (pintype "bidirectional"))
    )
    (net (code "55") (name "unconnected-(IC1A-PB8-Pad45)") (class "Default")
      (node (ref "IC1") (pin "45") (pinfunction "PB8_45") (pintype "bidirectional"))
    )
    (net (code "56") (name "unconnected-(IC1A-PB9-Pad46)") (class "Default")
      (node (ref "IC1") (pin "46") (pinfunction "PB9_46") (pintype "bidirectional"))
    )
    (net (code "57") (name "unconnected-(IC1A-PB10-Pad21)") (class "Default")
      (node (ref "IC1") (pin "21") (pinfunction "PB10_21") (pintype "bidirectional"))
    )
    (net (code "58") (name "unconnected-(IC1A-PB11-Pad22)") (class "Default")
      (node (ref "IC1") (pin "22") (pinfunction "PB11_22") (pintype "bidirectional"))
    )
    (net (code "59") (name "unconnected-(IC1A-PB12-Pad25)") (class "Default")
      (node (ref "IC1") (pin "25") (pinfunction "PB12_25") (pintype "bidirectional"))
    )
    (net (code "60") (name "unconnected-(IC1A-PB13-Pad26)") (class "Default")
      (node (ref "IC1") (pin "26") (pinfunction "PB13_26") (pintype "bidirectional"))
    )
    (net (code "61") (name "unconnected-(IC1A-PB14-Pad27)") (class "Default")
      (node (ref "IC1") (pin "27") (pinfunction "PB14_27") (pintype "bidirectional"))
    )
    (net (code "62") (name "unconnected-(IC1A-PB15-Pad28)") (class "Default")
      (node (ref "IC1") (pin "28") (pinfunction "PB15_28") (pintype "bidirectional"))
    )
    (net (code "63") (name "unconnected-(IC1A-PC14-Pad3)") (class "Default")
      (node (ref "IC1") (pin "3") (pinfunction "PC14_3") (pintype "bidirectional"))
    )
    (net (code "64") (name "unconnected-(IC1A-PC15-Pad4)") (class "Default")
      (node (ref "IC1") (pin "4") (pinfunction "PC15_4") (pintype "bidirectional"))
    )
    (net (code "65") (name "unconnected-(R10-Pad1)") (class "Default")
      (node (ref "R10") (pin "1") (pinfunction "1_1") (pintype "passive"))
    )
    (net (code "66") (name "unconnected-(R11-Pad1)") (class "Default")
      (node (ref "R11") (pin "1") (pinfunction "1_1") (pintype "passive"))
    )
  )
)
